# design.net
KiCad netlist of a schematic drawn in EAGLE
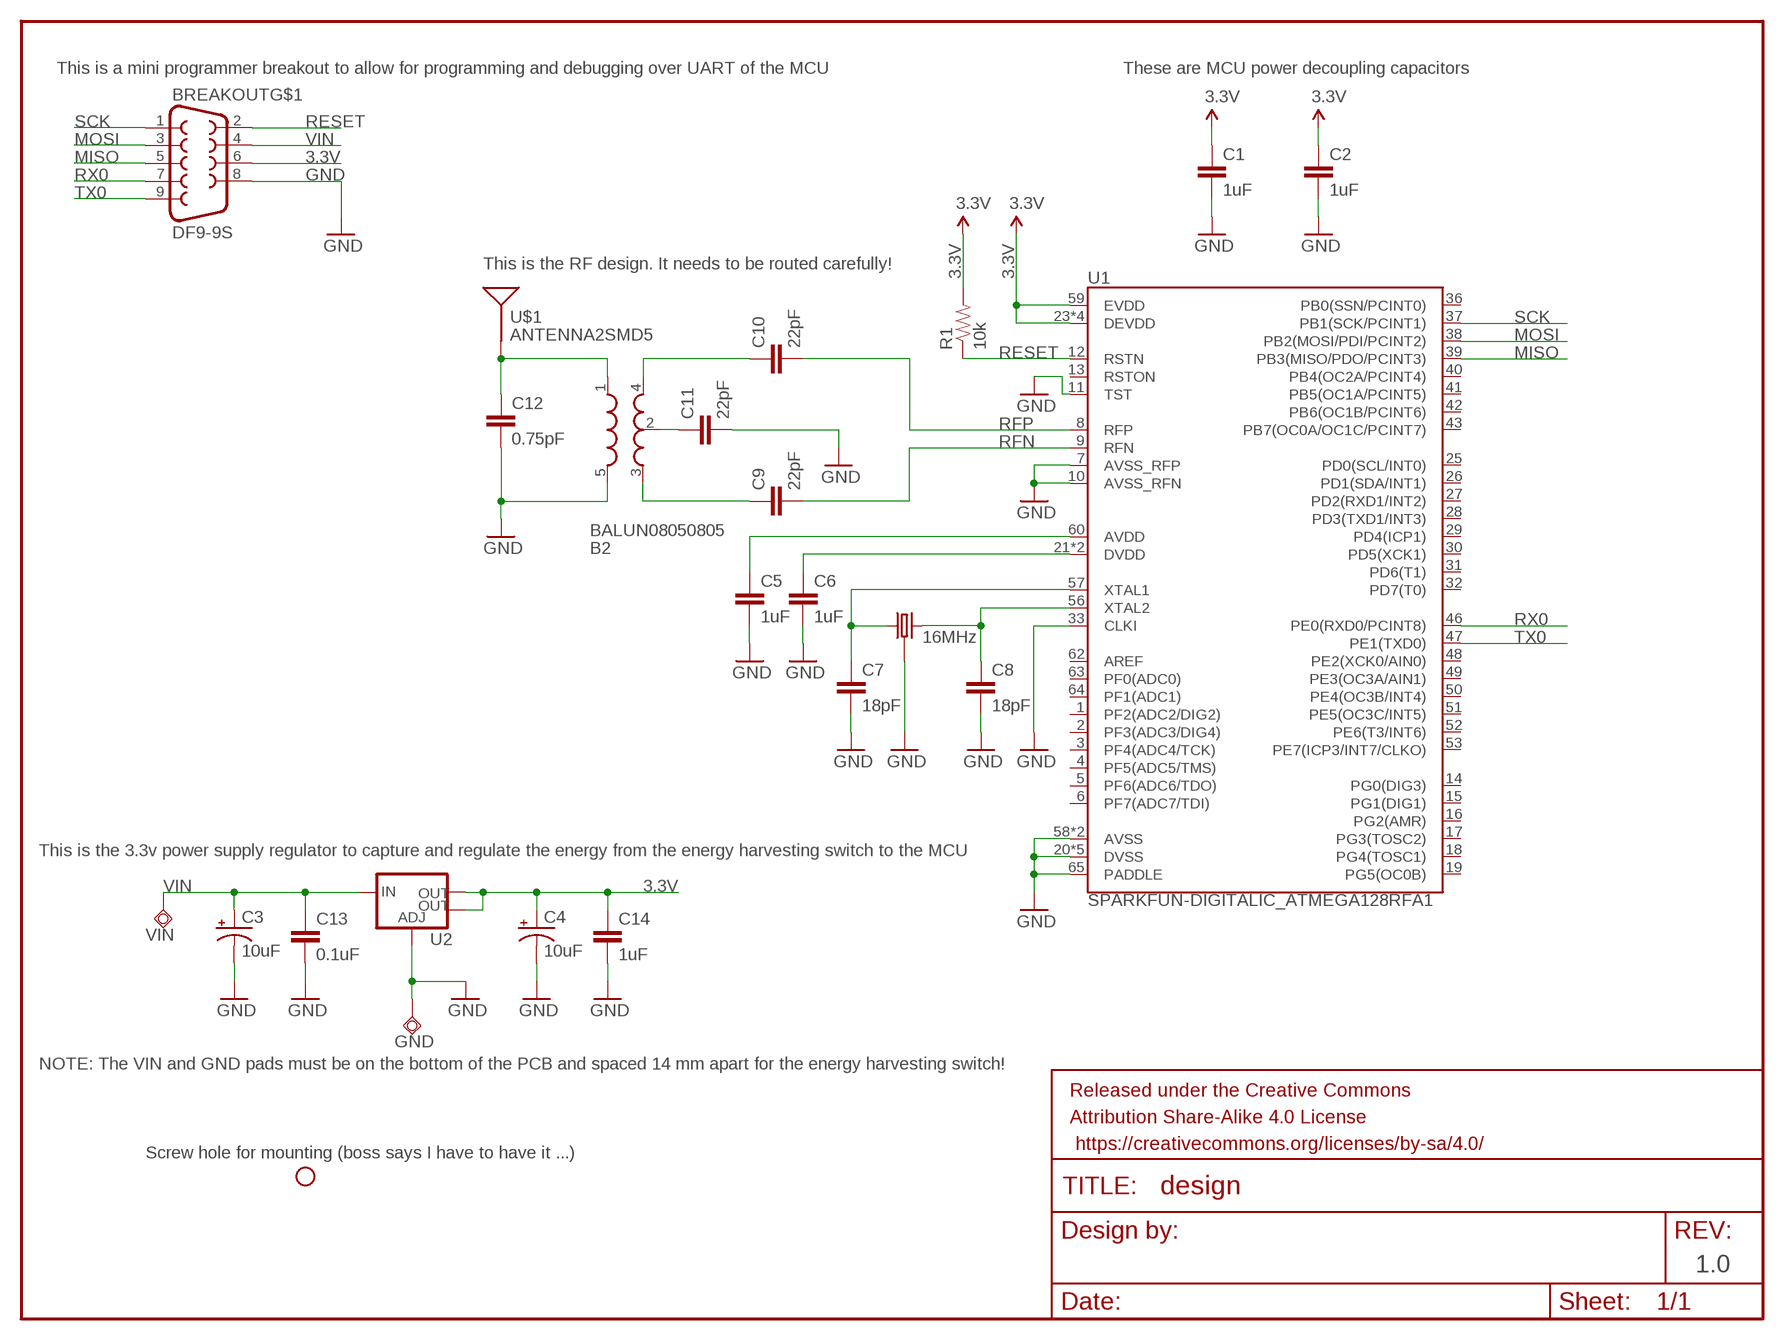
[diagram p0: schematic, sheet 1]

(export (version "E")
  (design (tool "Eeschema 10.0.6"))
  (components
    (comp (ref "B2")
      (value "BALUN08050805")
      (footprint "eagle-import:BALUN0805")
      (libsource (lib "eagle-import") (part "BALUN08050805"))
    )
    (comp (ref "BREAKOUT")
      (value "DF9-9S")
      (footprint "eagle-import:DF9-9S")
      (fields (field (name "MPN") " DF9-9S-1V(32) "))
      (libsource (lib "eagle-import") (part "DF9-9S"))
    )
    (comp (ref "C1")
      (value "1uF")
      (footprint "eagle-import:0603-CAP")
      (libsource (lib "eagle-import") (part "CAP0603-CAP"))
    )
    (comp (ref "C2")
      (value "1uF")
      (footprint "eagle-import:0603-CAP")
      (libsource (lib "eagle-import") (part "CAP0603-CAP"))
    )
    (comp (ref "C3")
      (value "10uF")
      (footprint "eagle-import:EIA3216")
      (libsource (lib "eagle-import") (part "CAP_POL1206"))
    )
    (comp (ref "C4")
      (value "10uF")
      (footprint "eagle-import:EIA3216")
      (libsource (lib "eagle-import") (part "CAP_POL1206"))
    )
    (comp (ref "C5")
      (value "1uF")
      (footprint "eagle-import:0603-CAP")
      (libsource (lib "eagle-import") (part "CAP0603-CAP"))
    )
    (comp (ref "C6")
      (value "1uF")
      (footprint "eagle-import:0603-CAP")
      (libsource (lib "eagle-import") (part "CAP0603-CAP"))
    )
    (comp (ref "C7")
      (value "18pF")
      (footprint "eagle-import:0603-CAP")
      (libsource (lib "eagle-import") (part "CAP0603-CAP"))
    )
    (comp (ref "C8")
      (value "18pF")
      (footprint "eagle-import:0603-CAP")
      (libsource (lib "eagle-import") (part "CAP0603-CAP"))
    )
    (comp (ref "C9")
      (value "22pF")
      (footprint "eagle-import:C0402")
      (libsource (lib "eagle-import") (part "C-EUC0402"))
    )
    (comp (ref "C10")
      (value "22pF")
      (footprint "eagle-import:C0402")
      (libsource (lib "eagle-import") (part "C-EUC0402"))
    )
    (comp (ref "C11")
      (value "22pF")
      (footprint "eagle-import:0603-CAP")
      (libsource (lib "eagle-import") (part "CAP0603-CAP"))
    )
    (comp (ref "C12")
      (value "0.75pF")
      (footprint "eagle-import:0603-CAP")
      (libsource (lib "eagle-import") (part "CAP0603-CAP"))
    )
    (comp (ref "C13")
      (value "0.1uF")
      (footprint "eagle-import:0603-CAP")
      (libsource (lib "eagle-import") (part "0.1UF-25V-5%(0603)"))
    )
    (comp (ref "C14")
      (value "1uF")
      (footprint "eagle-import:0603-CAP")
      (libsource (lib "eagle-import") (part "0.1UF-25V-5%(0603)"))
    )
    (comp (ref "FRAME1")
      (value "FRAME-LETTERNO_PACKAGE")
      (footprint "eagle-import:DUMMY")
      (fields (field (name "DESIGNER") "Nobody"))
      (libsource (lib "eagle-import") (part "FRAME-LETTERNO_PACKAGE"))
    )
    (comp (ref "GND")
      (value "TPSQTP20SQ")
      (footprint "eagle-import:TP20SQ")
      (libsource (lib "eagle-import") (part "TPSQTP20SQ"))
    )
    (comp (ref "H1")
      (value "STAND-OFF")
      (footprint "eagle-import:STAND-OFF")
      (libsource (lib "eagle-import") (part "STAND-OFF"))
    )
    (comp (ref "R1")
      (value "10k")
      (footprint "eagle-import:0603-RES")
      (libsource (lib "eagle-import") (part "RESISTOR0603-RES"))
    )
    (comp (ref "U$1")
      (value "ANTENNA2SMD5")
      (footprint "eagle-import:ANTENNA-CHIP5")
      (libsource (lib "eagle-import") (part "ANTENNA2SMD5"))
    )
    (comp (ref "U1")
      (value "SPARKFUN-DIGITALIC_ATMEGA128RFA1")
      (footprint "eagle-import:SPARKFUN-DIGITALIC_QFN-64")
      (libsource (lib "eagle-import") (part "SPARKFUN-DIGITALIC_ATMEGA128RFA1"))
    )
    (comp (ref "U2")
      (value "V_REG_LM1117SOT223")
      (footprint "eagle-import:SOT223")
      (libsource (lib "eagle-import") (part "V_REG_LM1117SOT223"))
    )
    (comp (ref "VIN")
      (value "TPSQTP20SQ")
      (footprint "eagle-import:TP20SQ")
      (libsource (lib "eagle-import") (part "TPSQTP20SQ"))
    )
    (comp (ref "Y2")
      (value "16MHz")
      (footprint "eagle-import:SPARKFUN-FREQCTRL_CRYSTAL-SMD-5X3")
      (libsource (lib "eagle-import") (part "CRYSTAL5X3.2"))
    )
  )
  (nets
    (net (code "1") (name "/MISO") (class "Default")
      (node (ref "BREAKOUT") (pin "5") (pinfunction "5_5") (pintype "passive"))
      (node (ref "U1") (pin "39") (pinfunction "PB3(MISO/PDO/PCINT3)_39") (pintype "bidirectional"))
    )
    (net (code "2") (name "/MOSI") (class "Default")
      (node (ref "BREAKOUT") (pin "3") (pinfunction "3_3") (pintype "passive"))
      (node (ref "U1") (pin "38") (pinfunction "PB2(MOSI/PDI/PCINT2)_38") (pintype "bidirectional"))
    )
    (net (code "3") (name "/RESET") (class "Default")
      (node (ref "BREAKOUT") (pin "2") (pinfunction "2_2") (pintype "passive"))
      (node (ref "R1") (pin "1") (pinfunction "1_1") (pintype "passive"))
      (node (ref "U1") (pin "12") (pinfunction "RSTN_12") (pintype "bidirectional"))
    )
    (net (code "4") (name "/RFN") (class "Default")
      (node (ref "C9") (pin "2") (pinfunction "2_2") (pintype "passive"))
      (node (ref "U1") (pin "9") (pinfunction "RFN_9") (pintype "bidirectional"))
    )
    (net (code "5") (name "/RFP") (class "Default")
      (node (ref "C10") (pin "2") (pinfunction "2_2") (pintype "passive"))
      (node (ref "U1") (pin "8") (pinfunction "RFP_8") (pintype "bidirectional"))
    )
    (net (code "6") (name "/RX0") (class "Default")
      (node (ref "BREAKOUT") (pin "7") (pinfunction "7_7") (pintype "passive"))
      (node (ref "U1") (pin "46") (pinfunction "PE0(RXD0/PCINT8)_46") (pintype "bidirectional"))
    )
    (net (code "7") (name "/SCK") (class "Default")
      (node (ref "BREAKOUT") (pin "1") (pinfunction "1_1") (pintype "passive"))
      (node (ref "U1") (pin "37") (pinfunction "PB1(SCK/PCINT1)_37") (pintype "bidirectional"))
    )
    (net (code "8") (name "/TX0") (class "Default")
      (node (ref "BREAKOUT") (pin "9") (pinfunction "9_9") (pintype "passive"))
      (node (ref "U1") (pin "47") (pinfunction "PE1(TXD0)_47") (pintype "bidirectional"))
    )
    (net (code "9") (name "/VIN") (class "Default")
      (node (ref "BREAKOUT") (pin "4") (pinfunction "4_4") (pintype "passive"))
      (node (ref "C13") (pin "1") (pinfunction "1_1") (pintype "passive"))
      (node (ref "C3") (pin "A") (pinfunction "+_A") (pintype "passive"))
      (node (ref "U2") (pin "3") (pinfunction "IN_3") (pintype "input"))
      (node (ref "VIN") (pin "TP") (pinfunction "TP_TP") (pintype "input"))
    )
    (net (code "10") (name "3.3V") (class "Default")
      (node (ref "BREAKOUT") (pin "6") (pinfunction "6_6") (pintype "passive"))
      (node (ref "C1") (pin "1") (pinfunction "1_1") (pintype "passive"))
      (node (ref "C14") (pin "1") (pinfunction "1_1") (pintype "passive"))
      (node (ref "C2") (pin "1") (pinfunction "1_1") (pintype "passive"))
      (node (ref "C4") (pin "A") (pinfunction "+_A") (pintype "passive"))
      (node (ref "R1") (pin "2") (pinfunction "2_2") (pintype "passive"))
      (node (ref "U1") (pin "23") (pinfunction "DEVDD_23") (pintype "bidirectional"))
      (node (ref "U1") (pin "34") (pinfunction "DEVDD_34") (pintype "bidirectional"))
      (node (ref "U1") (pin "44") (pinfunction "DEVDD_44") (pintype "bidirectional"))
      (node (ref "U1") (pin "54") (pinfunction "DEVDD_54") (pintype "bidirectional"))
      (node (ref "U1") (pin "59") (pinfunction "EVDD_59") (pintype "bidirectional"))
      (node (ref "U2") (pin "2") (pinfunction "OUT_2") (pintype "output"))
      (node (ref "U2") (pin "4") (pinfunction "OUT_4") (pintype "output"))
    )
    (net (code "11") (name "GND") (class "Default")
      (node (ref "B2") (pin "5") (pinfunction "GND_5") (pintype "bidirectional"))
      (node (ref "BREAKOUT") (pin "8") (pinfunction "8_8") (pintype "passive"))
      (node (ref "C1") (pin "2") (pinfunction "2_2") (pintype "passive"))
      (node (ref "C11") (pin "2") (pinfunction "2_2") (pintype "passive"))
      (node (ref "C12") (pin "2") (pinfunction "2_2") (pintype "passive"))
      (node (ref "C13") (pin "2") (pinfunction "2_2") (pintype "passive"))
      (node (ref "C14") (pin "2") (pinfunction "2_2") (pintype "passive"))
      (node (ref "C2") (pin "2") (pinfunction "2_2") (pintype "passive"))
      (node (ref "C3") (pin "C") (pinfunction "-_C") (pintype "passive"))
      (node (ref "C4") (pin "C") (pinfunction "-_C") (pintype "passive"))
      (node (ref "C5") (pin "2") (pinfunction "2_2") (pintype "passive"))
      (node (ref "C6") (pin "2") (pinfunction "2_2") (pintype "passive"))
      (node (ref "C7") (pin "2") (pinfunction "2_2") (pintype "passive"))
      (node (ref "C8") (pin "2") (pinfunction "2_2") (pintype "passive"))
      (node (ref "GND") (pin "TP") (pinfunction "TP_TP") (pintype "input"))
      (node (ref "U1") (pin "10") (pinfunction "AVSS_RFN_10") (pintype "bidirectional"))
      (node (ref "U1") (pin "11") (pinfunction "TST_11") (pintype "bidirectional"))
      (node (ref "U1") (pin "20") (pinfunction "DVSS_20") (pintype "bidirectional"))
      (node (ref "U1") (pin "24") (pinfunction "DVSS_24") (pintype "bidirectional"))
      (node (ref "U1") (pin "33") (pinfunction "CLKI_33") (pintype "bidirectional"))
      (node (ref "U1") (pin "35") (pinfunction "DVSS_35") (pintype "bidirectional"))
      (node (ref "U1") (pin "45") (pinfunction "DVSS_45") (pintype "bidirectional"))
      (node (ref "U1") (pin "55") (pinfunction "DVSS_55") (pintype "bidirectional"))
      (node (ref "U1") (pin "58") (pinfunction "AVSS_58") (pintype "bidirectional"))
      (node (ref "U1") (pin "61") (pinfunction "AVSS_61") (pintype "bidirectional"))
      (node (ref "U1") (pin "65") (pinfunction "PADDLE_65") (pintype "bidirectional"))
      (node (ref "U1") (pin "7") (pinfunction "AVSS_RFP_7") (pintype "bidirectional"))
      (node (ref "U2") (pin "1") (pinfunction "ADJ_1") (pintype "input"))
      (node (ref "Y2") (pin "2") (pinfunction "3_2") (pintype "passive"))
      (node (ref "Y2") (pin "4") (pinfunction "3_4") (pintype "passive"))
    )
    (net (code "12") (name "Net-(B2-GND-Pad2)") (class "Default")
      (node (ref "B2") (pin "2") (pinfunction "GND_2") (pintype "bidirectional"))
      (node (ref "C11") (pin "1") (pinfunction "1_1") (pintype "passive"))
    )
    (net (code "13") (name "Net-(B2-IN)") (class "Default")
      (node (ref "B2") (pin "1") (pinfunction "IN_1") (pintype "bidirectional"))
      (node (ref "C12") (pin "1") (pinfunction "1_1") (pintype "passive"))
      (node (ref "U$1") (pin "FEED") (pinfunction "SIGNAL_FEED") (pintype "bidirectional"))
    )
    (net (code "14") (name "Net-(B2-OUT1)") (class "Default")
      (node (ref "B2") (pin "4") (pinfunction "OUT1_4") (pintype "bidirectional"))
      (node (ref "C10") (pin "1") (pinfunction "1_1") (pintype "passive"))
    )
    (net (code "15") (name "Net-(B2-OUT2)") (class "Default")
      (node (ref "B2") (pin "3") (pinfunction "OUT2_3") (pintype "bidirectional"))
      (node (ref "C9") (pin "1") (pinfunction "1_1") (pintype "passive"))
    )
    (net (code "16") (name "Net-(C6-Pad1)") (class "Default")
      (node (ref "C6") (pin "1") (pinfunction "1_1") (pintype "passive"))
      (node (ref "U1") (pin "21") (pinfunction "DVDD_21") (pintype "bidirectional"))
      (node (ref "U1") (pin "22") (pinfunction "DVDD_22") (pintype "bidirectional"))
    )
    (net (code "17") (name "Net-(U1-AVDD)") (class "Default")
      (node (ref "C5") (pin "1") (pinfunction "1_1") (pintype "passive"))
      (node (ref "U1") (pin "60") (pinfunction "AVDD_60") (pintype "bidirectional"))
    )
    (net (code "18") (name "Net-(U1-XTAL1)") (class "Default")
      (node (ref "C7") (pin "1") (pinfunction "1_1") (pintype "passive"))
      (node (ref "U1") (pin "57") (pinfunction "XTAL1_57") (pintype "bidirectional"))
      (node (ref "Y2") (pin "1") (pinfunction "1_1") (pintype "passive"))
    )
    (net (code "19") (name "Net-(U1-XTAL2)") (class "Default")
      (node (ref "C8") (pin "1") (pinfunction "1_1") (pintype "passive"))
      (node (ref "U1") (pin "56") (pinfunction "XTAL2_56") (pintype "bidirectional"))
      (node (ref "Y2") (pin "3") (pinfunction "2_3") (pintype "passive"))
    )
    (net (code "20") (name "unconnected-(U1-AREF-Pad62)") (class "Default")
      (node (ref "U1") (pin "62") (pinfunction "AREF_62") (pintype "bidirectional"))
    )
    (net (code "21") (name "unconnected-(U1-PB0(SSN{slash}PCINT0)-Pad36)") (class "Default")
      (node (ref "U1") (pin "36") (pinfunction "PB0(SSN/PCINT0)_36") (pintype "bidirectional"))
    )
    (net (code "22") (name "unconnected-(U1-PB4(OC2A{slash}PCINT4)-Pad40)") (class "Default")
      (node (ref "U1") (pin "40") (pinfunction "PB4(OC2A/PCINT4)_40") (pintype "bidirectional"))
    )
    (net (code "23") (name "unconnected-(U1-PB5(OC1A{slash}PCINT5)-Pad41)") (class "Default")
      (node (ref "U1") (pin "41") (pinfunction "PB5(OC1A/PCINT5)_41") (pintype "bidirectional"))
    )
    (net (code "24") (name "unconnected-(U1-PB6(OC1B{slash}PCINT6)-Pad42)") (class "Default")
      (node (ref "U1") (pin "42") (pinfunction "PB6(OC1B/PCINT6)_42") (pintype "bidirectional"))
    )
    (net (code "25") (name "unconnected-(U1-PB7(OC0A{slash}OC1C{slash}PCINT7)-Pad43)") (class "Default")
      (node (ref "U1") (pin "43") (pinfunction "PB7(OC0A/OC1C/PCINT7)_43") (pintype "bidirectional"))
    )
    (net (code "26") (name "unconnected-(U1-PD0(SCL{slash}INT0)-Pad25)") (class "Default")
      (node (ref "U1") (pin "25") (pinfunction "PD0(SCL/INT0)_25") (pintype "bidirectional"))
    )
    (net (code "27") (name "unconnected-(U1-PD1(SDA{slash}INT1)-Pad26)") (class "Default")
      (node (ref "U1") (pin "26") (pinfunction "PD1(SDA/INT1)_26") (pintype "bidirectional"))
    )
    (net (code "28") (name "unconnected-(U1-PD2(RXD1{slash}INT2)-Pad27)") (class "Default")
      (node (ref "U1") (pin "27") (pinfunction "PD2(RXD1/INT2)_27") (pintype "bidirectional"))
    )
    (net (code "29") (name "unconnected-(U1-PD3(TXD1{slash}INT3)-Pad28)") (class "Default")
      (node (ref "U1") (pin "28") (pinfunction "PD3(TXD1/INT3)_28") (pintype "bidirectional"))
    )
    (net (code "30") (name "unconnected-(U1-PD4(ICP1)-Pad29)") (class "Default")
      (node (ref "U1") (pin "29") (pinfunction "PD4(ICP1)_29") (pintype "bidirectional"))
    )
    (net (code "31") (name "unconnected-(U1-PD5(XCK1)-Pad30)") (class "Default")
      (node (ref "U1") (pin "30") (pinfunction "PD5(XCK1)_30") (pintype "bidirectional"))
    )
    (net (code "32") (name "unconnected-(U1-PD6(T1)-Pad31)") (class "Default")
      (node (ref "U1") (pin "31") (pinfunction "PD6(T1)_31") (pintype "bidirectional"))
    )
    (net (code "33") (name "unconnected-(U1-PD7(T0)-Pad32)") (class "Default")
      (node (ref "U1") (pin "32") (pinfunction "PD7(T0)_32") (pintype "bidirectional"))
    )
    (net (code "34") (name "unconnected-(U1-PE2(XCK0{slash}AIN0)-Pad48)") (class "Default")
      (node (ref "U1") (pin "48") (pinfunction "PE2(XCK0/AIN0)_48") (pintype "bidirectional"))
    )
    (net (code "35") (name "unconnected-(U1-PE3(OC3A{slash}AIN1)-Pad49)") (class "Default")
      (node (ref "U1") (pin "49") (pinfunction "PE3(OC3A/AIN1)_49") (pintype "bidirectional"))
    )
    (net (code "36") (name "unconnected-(U1-PE4(OC3B{slash}INT4)-Pad50)") (class "Default")
      (node (ref "U1") (pin "50") (pinfunction "PE4(OC3B/INT4)_50") (pintype "bidirectional"))
    )
    (net (code "37") (name "unconnected-(U1-PE5(OC3C{slash}INT5)-Pad51)") (class "Default")
      (node (ref "U1") (pin "51") (pinfunction "PE5(OC3C/INT5)_51") (pintype "bidirectional"))
    )
    (net (code "38") (name "unconnected-(U1-PE6(T3{slash}INT6)-Pad52)") (class "Default")
      (node (ref "U1") (pin "52") (pinfunction "PE6(T3/INT6)_52") (pintype "bidirectional"))
    )
    (net (code "39") (name "unconnected-(U1-PE7(ICP3{slash}INT7{slash}CLKO)-Pad53)") (class "Default")
      (node (ref "U1") (pin "53") (pinfunction "PE7(ICP3/INT7/CLKO)_53") (pintype "bidirectional"))
    )
    (net (code "40") (name "unconnected-(U1-PF0(ADC0)-Pad63)") (class "Default")
      (node (ref "U1") (pin "63") (pinfunction "PF0(ADC0)_63") (pintype "bidirectional"))
    )
    (net (code "41") (name "unconnected-(U1-PF1(ADC1)-Pad64)") (class "Default")
      (node (ref "U1") (pin "64") (pinfunction "PF1(ADC1)_64") (pintype "bidirectional"))
    )
    (net (code "42") (name "unconnected-(U1-PF2(ADC2{slash}DIG2)-Pad1)") (class "Default")
      (node (ref "U1") (pin "1") (pinfunction "PF2(ADC2/DIG2)_1") (pintype "bidirectional"))
    )
    (net (code "43") (name "unconnected-(U1-PF3(ADC3{slash}DIG4)-Pad2)") (class "Default")
      (node (ref "U1") (pin "2") (pinfunction "PF3(ADC3/DIG4)_2") (pintype "bidirectional"))
    )
    (net (code "44") (name "unconnected-(U1-PF4(ADC4{slash}TCK)-Pad3)") (class "Default")
      (node (ref "U1") (pin "3") (pinfunction "PF4(ADC4/TCK)_3") (pintype "bidirectional"))
    )
    (net (code "45") (name "unconnected-(U1-PF5(ADC5{slash}TMS)-Pad4)") (class "Default")
      (node (ref "U1") (pin "4") (pinfunction "PF5(ADC5/TMS)_4") (pintype "bidirectional"))
    )
    (net (code "46") (name "unconnected-(U1-PF6(ADC6{slash}TDO)-Pad5)") (class "Default")
      (node (ref "U1") (pin "5") (pinfunction "PF6(ADC6/TDO)_5") (pintype "bidirectional"))
    )
    (net (code "47") (name "unconnected-(U1-PF7(ADC7{slash}TDI)-Pad6)") (class "Default")
      (node (ref "U1") (pin "6") (pinfunction "PF7(ADC7/TDI)_6") (pintype "bidirectional"))
    )
    (net (code "48") (name "unconnected-(U1-PG0(DIG3)-Pad14)") (class "Default")
      (node (ref "U1") (pin "14") (pinfunction "PG0(DIG3)_14") (pintype "bidirectional"))
    )
    (net (code "49") (name "unconnected-(U1-PG1(DIG1)-Pad15)") (class "Default")
      (node (ref "U1") (pin "15") (pinfunction "PG1(DIG1)_15") (pintype "bidirectional"))
    )
    (net (code "50") (name "unconnected-(U1-PG2(AMR)-Pad16)") (class "Default")
      (node (ref "U1") (pin "16") (pinfunction "PG2(AMR)_16") (pintype "bidirectional"))
    )
    (net (code "51") (name "unconnected-(U1-PG3(TOSC2)-Pad17)") (class "Default")
      (node (ref "U1") (pin "17") (pinfunction "PG3(TOSC2)_17") (pintype "bidirectional"))
    )
    (net (code "52") (name "unconnected-(U1-PG4(TOSC1)-Pad18)") (class "Default")
      (node (ref "U1") (pin "18") (pinfunction "PG4(TOSC1)_18") (pintype "bidirectional"))
    )
    (net (code "53") (name "unconnected-(U1-PG5(OC0B)-Pad19)") (class "Default")
      (node (ref "U1") (pin "19") (pinfunction "PG5(OC0B)_19") (pintype "bidirectional"))
    )
    (net (code "54") (name "unconnected-(U1-RSTON-Pad13)") (class "Default")
      (node (ref "U1") (pin "13") (pinfunction "RSTON_13") (pintype "bidirectional"))
    )
  )
)
